# analog_homoThermistor_3xChannel_R1.net
KiCad netlist of a schematic drawn in EAGLE
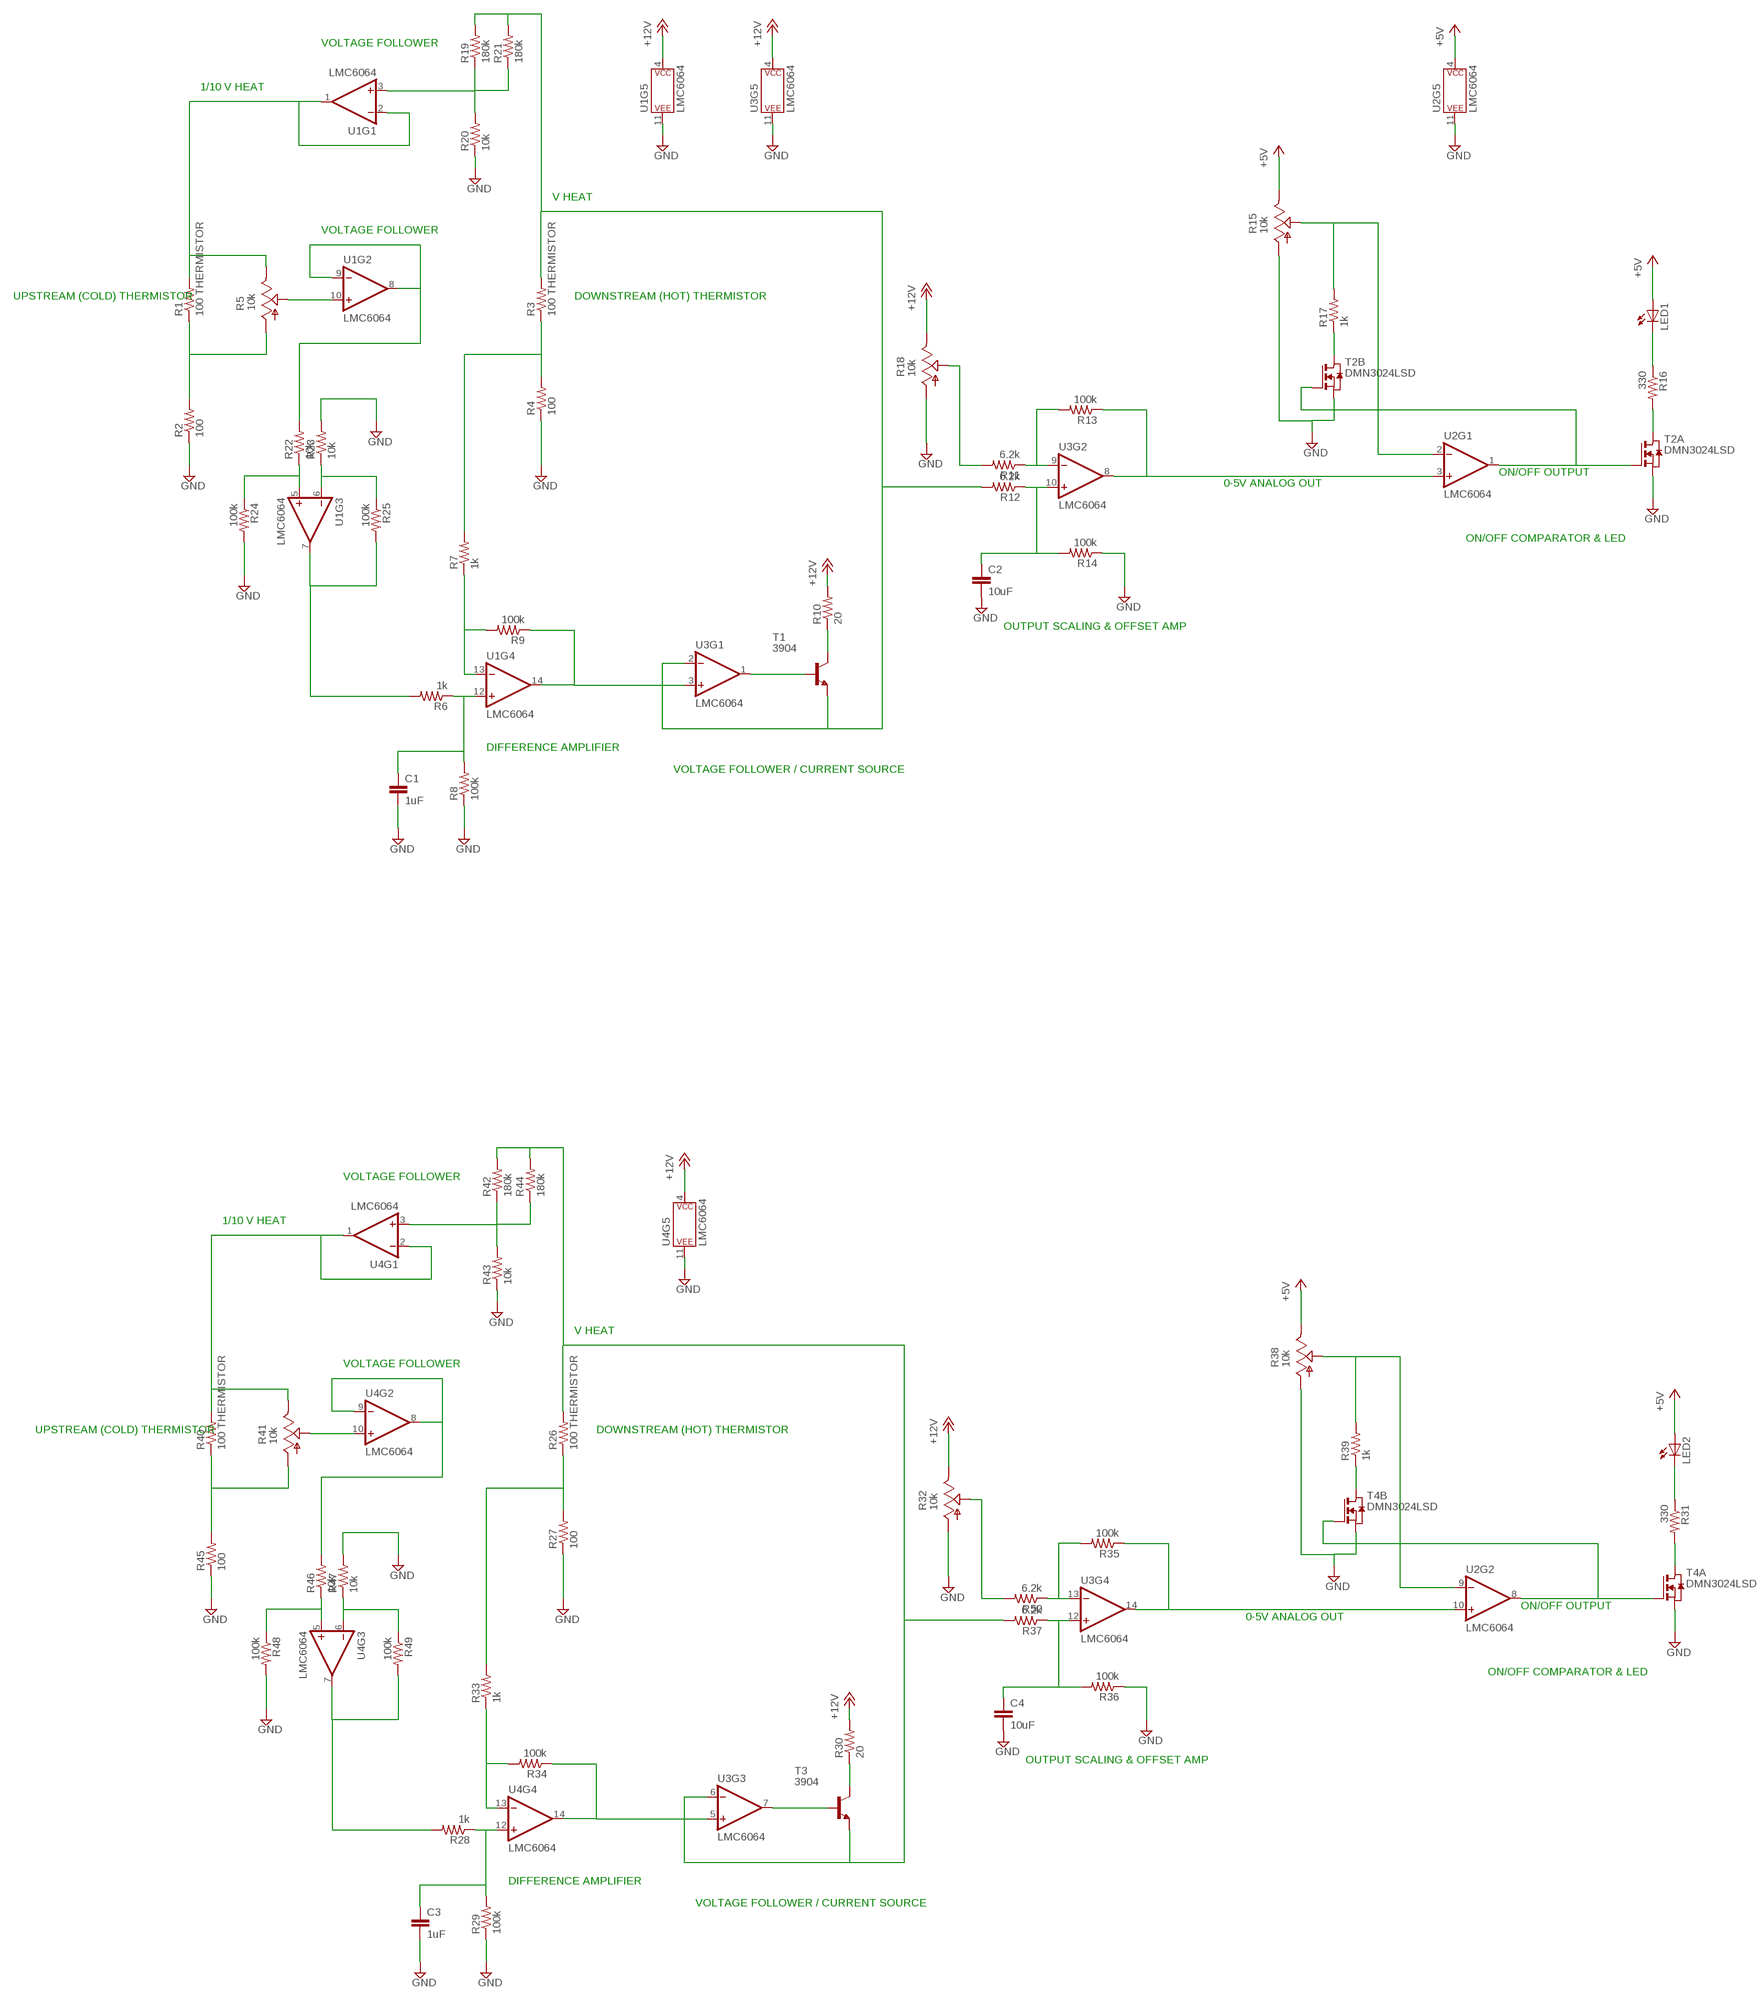
[diagram p0: schematic, sheet 1, part 1 of 2]
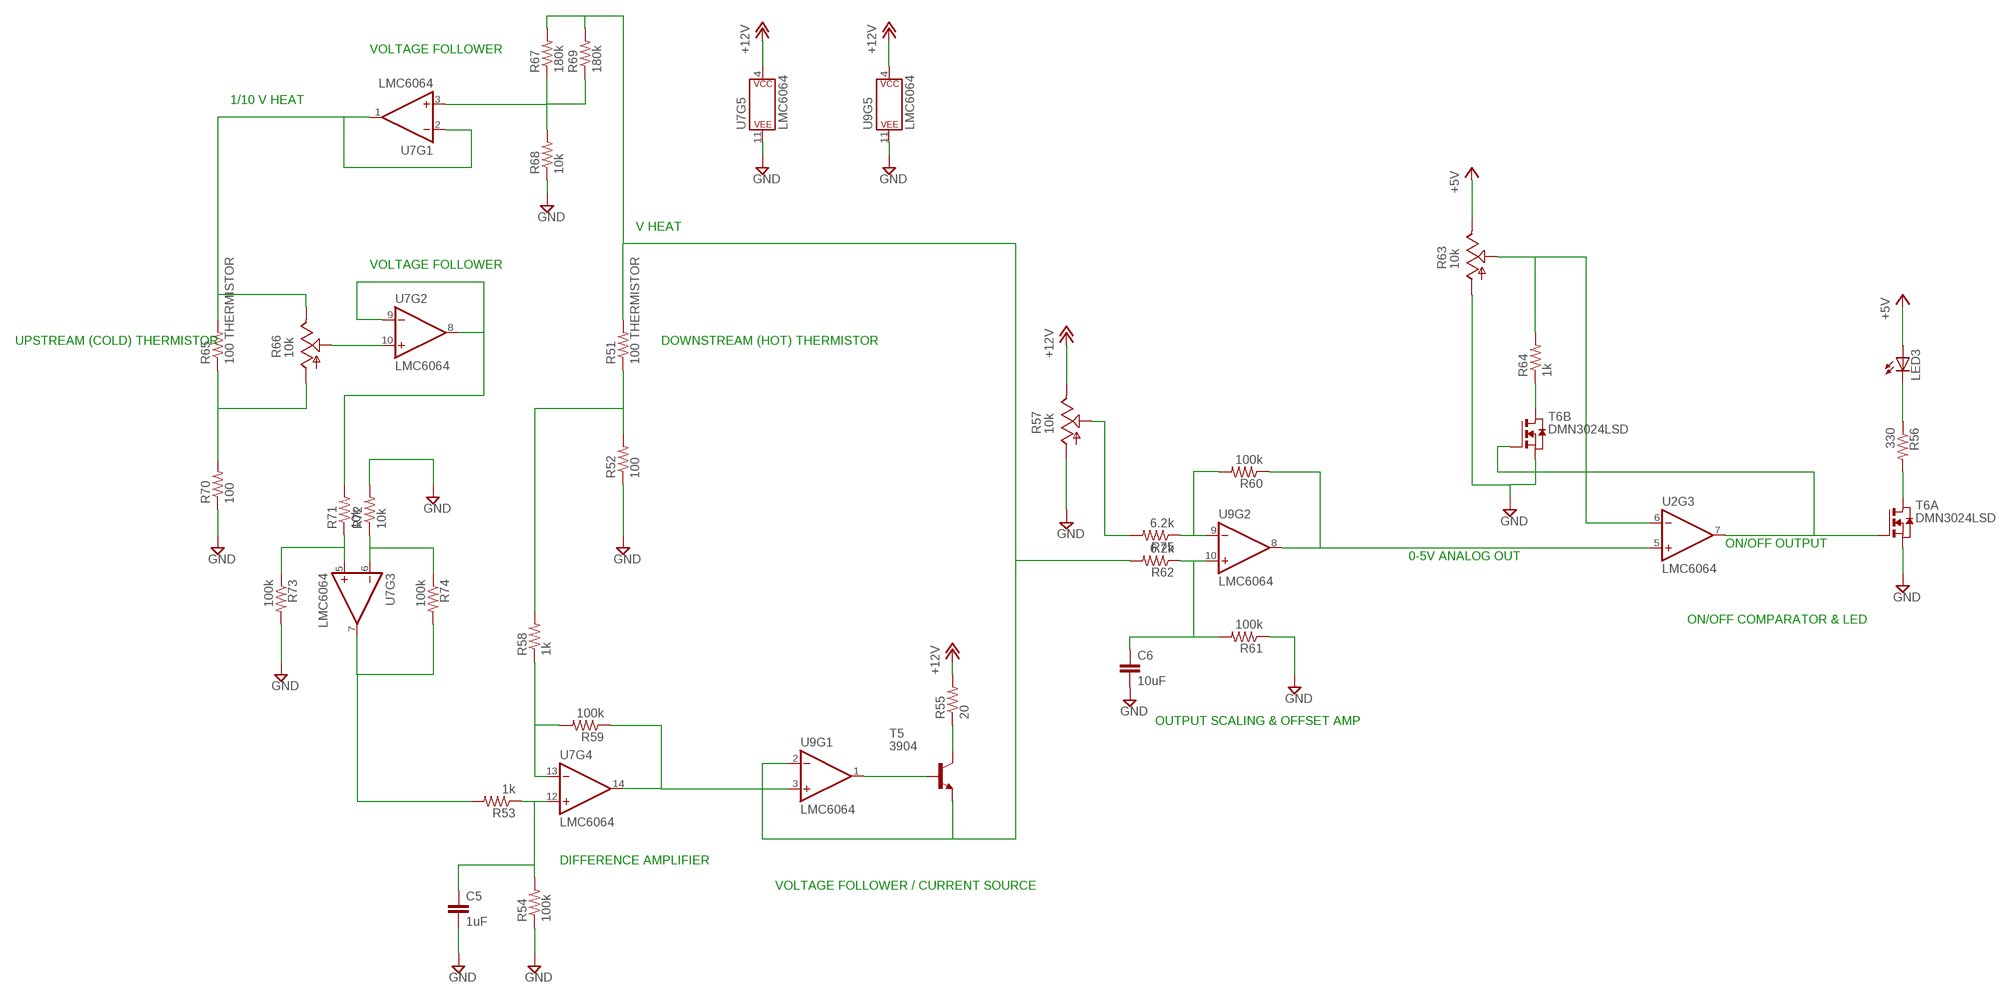
[diagram p1: schematic, sheet 1, part 2 of 2]

(export (version "E")
  (design (tool "Eeschema 10.0.6"))
  (components
    (comp (ref "C1")
      (value "1uF")
      (footprint "eagle-import:C0603")
      (fields
        (field (name "MF") "Murata Electronics North America")
        (field (name "MPN") "GRM188R61C105KA93D")
      )
      (libsource (lib "eagle-import") (part "C-EUC0603"))
    )
    (comp (ref "C2")
      (value "10uF")
      (footprint "eagle-import:C0603")
      (fields
        (field (name "MF") "Murata Electronics North America")
        (field (name "MPN") "GRM188C81C106MA73D")
      )
      (libsource (lib "eagle-import") (part "C-EUC0603"))
    )
    (comp (ref "C3")
      (value "1uF")
      (footprint "eagle-import:C0603")
      (fields
        (field (name "MF") "Murata Electronics North America")
        (field (name "MPN") "GRM188R61C105KA93D")
      )
      (libsource (lib "eagle-import") (part "C-EUC0603"))
    )
    (comp (ref "C4")
      (value "10uF")
      (footprint "eagle-import:C0603")
      (fields
        (field (name "MF") "Murata Electronics North America")
        (field (name "MPN") "GRM188C81C106MA73D")
      )
      (libsource (lib "eagle-import") (part "C-EUC0603"))
    )
    (comp (ref "C5")
      (value "1uF")
      (footprint "eagle-import:C0603")
      (fields
        (field (name "MF") "Murata Electronics North America")
        (field (name "MPN") "GRM188R61C105KA93D")
      )
      (libsource (lib "eagle-import") (part "C-EUC0603"))
    )
    (comp (ref "C6")
      (value "10uF")
      (footprint "eagle-import:C0603")
      (fields
        (field (name "MF") "Murata Electronics North America")
        (field (name "MPN") "GRM188C81C106MA73D")
      )
      (libsource (lib "eagle-import") (part "C-EUC0603"))
    )
    (comp (ref "LED1")
      (value "LEDCHIPLED_1206")
      (footprint "eagle-import:CHIPLED_1206")
      (fields (field (name "MF") "Lite-On Inc.") (field (name "MPN") "LTST-C150GKT"))
      (libsource (lib "eagle-import") (part "LEDCHIPLED_1206"))
    )
    (comp (ref "LED2")
      (value "LEDCHIPLED_1206")
      (footprint "eagle-import:CHIPLED_1206")
      (fields (field (name "MF") "Lite-On Inc.") (field (name "MPN") "LTST-C150GKT"))
      (libsource (lib "eagle-import") (part "LEDCHIPLED_1206"))
    )
    (comp (ref "LED3")
      (value "LEDCHIPLED_1206")
      (footprint "eagle-import:CHIPLED_1206")
      (fields (field (name "MF") "Lite-On Inc.") (field (name "MPN") "LTST-C150GKT"))
      (libsource (lib "eagle-import") (part "LEDCHIPLED_1206"))
    )
    (comp (ref "R1")
      (value "100 THERMISTOR")
      (footprint "eagle-import:R0603")
      (fields
        (field (name "DISTR") "Digikey")
        (field (name "DISTRPN") "490-2434-1-ND")
        (field (name "MF") "Murata Electronics North America")
        (field (name "MPN") "NCP18XF101J03RB")
      )
      (libsource (lib "eagle-import") (part "R-US_R0603"))
    )
    (comp (ref "R2")
      (value "100")
      (footprint "eagle-import:R0603")
      (fields (field (name "MF") "Panasonic Electronic Components") (field (name "MPN") "ERJ-PA3F1000V"))
      (libsource (lib "eagle-import") (part "R-US_R0603"))
    )
    (comp (ref "R3")
      (value "100 THERMISTOR")
      (footprint "eagle-import:R0603")
      (fields
        (field (name "DISTR") "Digikey")
        (field (name "DISTRPN") "490-2434-1-ND")
        (field (name "MF") "Murata Electronics North America")
        (field (name "MPN") "NCP18XF101J03RB")
      )
      (libsource (lib "eagle-import") (part "R-US_R0603"))
    )
    (comp (ref "R4")
      (value "100")
      (footprint "eagle-import:R0603")
      (fields (field (name "MF") "Panasonic Electronic Components") (field (name "MPN") "ERJ-PA3F1000V"))
      (libsource (lib "eagle-import") (part "R-US_R0603"))
    )
    (comp (ref "R5")
      (value "10k")
      (footprint "eagle-import:SM-42_43W")
      (fields (field (name "MF") "Copal Electronics Inc.") (field (name "MPN") "SM-42TW103"))
      (libsource (lib "eagle-import") (part "TRIM_US-SM-42/43W"))
    )
    (comp (ref "R6")
      (value "1k")
      (footprint "eagle-import:R0603")
      (fields (field (name "MF") "Panasonic Electronic Components") (field (name "MPN") "ERJ-PA3F1001V"))
      (libsource (lib "eagle-import") (part "R-US_R0603"))
    )
    (comp (ref "R7")
      (value "1k")
      (footprint "eagle-import:R0603")
      (fields (field (name "MF") "Panasonic Electronic Components") (field (name "MPN") "ERJ-PA3F1001V"))
      (libsource (lib "eagle-import") (part "R-US_R0603"))
    )
    (comp (ref "R8")
      (value "100k")
      (footprint "eagle-import:R0603")
      (fields (field (name "MF") "Panasonic Electronic Components") (field (name "MPN") "ERJ-PA3F1003V"))
      (libsource (lib "eagle-import") (part "R-US_R0603"))
    )
    (comp (ref "R9")
      (value "100k")
      (footprint "eagle-import:R0603")
      (fields (field (name "MF") "Panasonic Electronic Components") (field (name "MPN") "ERJ-PA3F1003V"))
      (libsource (lib "eagle-import") (part "R-US_R0603"))
    )
    (comp (ref "R10")
      (value "20")
      (footprint "eagle-import:R0603")
      (fields (field (name "MF") "Panasonic Electronic Components") (field (name "MPN") "ERJ-PA3F20R0V"))
      (libsource (lib "eagle-import") (part "R-US_R0603"))
    )
    (comp (ref "R11")
      (value "6.2k")
      (footprint "eagle-import:R0603")
      (fields (field (name "MF") "Panasonic Electronic Components") (field (name "MPN") "ERJ-PA3F6201V"))
      (libsource (lib "eagle-import") (part "R-US_R0603"))
    )
    (comp (ref "R12")
      (value "6.2k")
      (footprint "eagle-import:R0603")
      (fields (field (name "MF") "Panasonic Electronic Components") (field (name "MPN") "ERJ-PA3F6201V"))
      (libsource (lib "eagle-import") (part "R-US_R0603"))
    )
    (comp (ref "R13")
      (value "100k")
      (footprint "eagle-import:R0603")
      (fields (field (name "MF") "Panasonic Electronic Components") (field (name "MPN") "ERJ-PA3F1003V"))
      (libsource (lib "eagle-import") (part "R-US_R0603"))
    )
    (comp (ref "R14")
      (value "100k")
      (footprint "eagle-import:R0603")
      (fields (field (name "MF") "Panasonic Electronic Components") (field (name "MPN") "ERJ-PA3F1003V"))
      (libsource (lib "eagle-import") (part "R-US_R0603"))
    )
    (comp (ref "R15")
      (value "10k")
      (footprint "eagle-import:SM-42_43W")
      (fields (field (name "MF") "Copal Electronics Inc.") (field (name "MPN") "SM-42TW103"))
      (libsource (lib "eagle-import") (part "TRIM_US-SM-42/43W"))
    )
    (comp (ref "R16")
      (value "330")
      (footprint "eagle-import:R0603")
      (fields (field (name "MF") "Panasonic Electronic Components") (field (name "MPN") "ERJ-PA3F3300V"))
      (libsource (lib "eagle-import") (part "R-US_R0603"))
    )
    (comp (ref "R17")
      (value "1k")
      (footprint "eagle-import:R0603")
      (fields (field (name "MF") "Panasonic Electronic Components") (field (name "MPN") "ERJ-PA3F1001V"))
      (libsource (lib "eagle-import") (part "R-US_R0603"))
    )
    (comp (ref "R18")
      (value "10k")
      (footprint "eagle-import:SM-42_43W")
      (fields (field (name "MF") "Copal Electronics Inc.") (field (name "MPN") "SM-42TW103"))
      (libsource (lib "eagle-import") (part "TRIM_US-SM-42/43W"))
    )
    (comp (ref "R19")
      (value "180k")
      (footprint "eagle-import:R0603")
      (fields (field (name "MF") "Panasonic Electronic Components") (field (name "MPN") "ERJ-PA3F1803V"))
      (libsource (lib "eagle-import") (part "R-US_R0603"))
    )
    (comp (ref "R20")
      (value "10k")
      (footprint "eagle-import:R0603")
      (fields (field (name "MF") "Panasonic Electronic Components") (field (name "MPN") "ERJ-PA3F1002V"))
      (libsource (lib "eagle-import") (part "R-US_R0603"))
    )
    (comp (ref "R21")
      (value "180k")
      (footprint "eagle-import:R0603")
      (fields (field (name "MF") "Panasonic Electronic Components") (field (name "MPN") "ERJ-PA3F1803V"))
      (libsource (lib "eagle-import") (part "R-US_R0603"))
    )
    (comp (ref "R22")
      (value "10k")
      (footprint "eagle-import:R0603")
      (fields (field (name "MF") "Panasonic Electronic Components") (field (name "MPN") "ERJ-PA3F1002V"))
      (libsource (lib "eagle-import") (part "R-US_R0603"))
    )
    (comp (ref "R23")
      (value "10k")
      (footprint "eagle-import:R0603")
      (fields (field (name "MF") "Panasonic Electronic Components") (field (name "MPN") "ERJ-PA3F1002V"))
      (libsource (lib "eagle-import") (part "R-US_R0603"))
    )
    (comp (ref "R24")
      (value "100k")
      (footprint "eagle-import:R0603")
      (fields (field (name "MF") "Panasonic Electronic Components") (field (name "MPN") "ERJ-PA3F1003V"))
      (libsource (lib "eagle-import") (part "R-US_R0603"))
    )
    (comp (ref "R25")
      (value "100k")
      (footprint "eagle-import:R0603")
      (fields (field (name "MF") "Panasonic Electronic Components") (field (name "MPN") "ERJ-PA3F1003V"))
      (libsource (lib "eagle-import") (part "R-US_R0603"))
    )
    (comp (ref "R26")
      (value "100 THERMISTOR")
      (footprint "eagle-import:R0603")
      (fields
        (field (name "DISTR") "Digikey")
        (field (name "DISTRPN") "490-2434-1-ND")
        (field (name "MF") "Murata Electronics North America")
        (field (name "MPN") "NCP18XF101J03RB")
      )
      (libsource (lib "eagle-import") (part "R-US_R0603"))
    )
    (comp (ref "R27")
      (value "100")
      (footprint "eagle-import:R0603")
      (fields (field (name "MF") "Panasonic Electronic Components") (field (name "MPN") "ERJ-PA3F1000V"))
      (libsource (lib "eagle-import") (part "R-US_R0603"))
    )
    (comp (ref "R28")
      (value "1k")
      (footprint "eagle-import:R0603")
      (fields (field (name "MF") "Panasonic Electronic Components") (field (name "MPN") "ERJ-PA3F1001V"))
      (libsource (lib "eagle-import") (part "R-US_R0603"))
    )
    (comp (ref "R29")
      (value "100k")
      (footprint "eagle-import:R0603")
      (fields (field (name "MF") "Panasonic Electronic Components") (field (name "MPN") "ERJ-PA3F1003V"))
      (libsource (lib "eagle-import") (part "R-US_R0603"))
    )
    (comp (ref "R30")
      (value "20")
      (footprint "eagle-import:R0603")
      (fields (field (name "MF") "Panasonic Electronic Components") (field (name "MPN") "ERJ-PA3F20R0V"))
      (libsource (lib "eagle-import") (part "R-US_R0603"))
    )
    (comp (ref "R31")
      (value "330")
      (footprint "eagle-import:R0603")
      (fields (field (name "MF") "Panasonic Electronic Components") (field (name "MPN") "ERJ-PA3F3300V"))
      (libsource (lib "eagle-import") (part "R-US_R0603"))
    )
    (comp (ref "R32")
      (value "10k")
      (footprint "eagle-import:SM-42_43W")
      (fields (field (name "MF") "Copal Electronics Inc.") (field (name "MPN") "SM-42TW103"))
      (libsource (lib "eagle-import") (part "TRIM_US-SM-42/43W"))
    )
    (comp (ref "R33")
      (value "1k")
      (footprint "eagle-import:R0603")
      (fields (field (name "MF") "Panasonic Electronic Components") (field (name "MPN") "ERJ-PA3F1001V"))
      (libsource (lib "eagle-import") (part "R-US_R0603"))
    )
    (comp (ref "R34")
      (value "100k")
      (footprint "eagle-import:R0603")
      (fields (field (name "MF") "Panasonic Electronic Components") (field (name "MPN") "ERJ-PA3F1003V"))
      (libsource (lib "eagle-import") (part "R-US_R0603"))
    )
    (comp (ref "R35")
      (value "100k")
      (footprint "eagle-import:R0603")
      (fields (field (name "MF") "Panasonic Electronic Components") (field (name "MPN") "ERJ-PA3F1003V"))
      (libsource (lib "eagle-import") (part "R-US_R0603"))
    )
    (comp (ref "R36")
      (value "100k")
      (footprint "eagle-import:R0603")
      (fields (field (name "MF") "Panasonic Electronic Components") (field (name "MPN") "ERJ-PA3F1003V"))
      (libsource (lib "eagle-import") (part "R-US_R0603"))
    )
    (comp (ref "R37")
      (value "6.2k")
      (footprint "eagle-import:R0603")
      (fields (field (name "MF") "Panasonic Electronic Components") (field (name "MPN") "ERJ-PA3F6201V"))
      (libsource (lib "eagle-import") (part "R-US_R0603"))
    )
    (comp (ref "R38")
      (value "10k")
      (footprint "eagle-import:SM-42_43W")
      (fields (field (name "MF") "Copal Electronics Inc.") (field (name "MPN") "SM-42TW103"))
      (libsource (lib "eagle-import") (part "TRIM_US-SM-42/43W"))
    )
    (comp (ref "R39")
      (value "1k")
      (footprint "eagle-import:R0603")
      (fields (field (name "MF") "Panasonic Electronic Components") (field (name "MPN") "ERJ-PA3F1001V"))
      (libsource (lib "eagle-import") (part "R-US_R0603"))
    )
    (comp (ref "R40")
      (value "100 THERMISTOR")
      (footprint "eagle-import:R0603")
      (fields
        (field (name "DISTR") "Digikey")
        (field (name "DISTRPN") "490-2434-1-ND")
        (field (name "MF") "Murata Electronics North America")
        (field (name "MPN") "NCP18XF101J03RB")
      )
      (libsource (lib "eagle-import") (part "R-US_R0603"))
    )
    (comp (ref "R41")
      (value "10k")
      (footprint "eagle-import:SM-42_43W")
      (fields (field (name "MF") "Copal Electronics Inc.") (field (name "MPN") "SM-42TW103"))
      (libsource (lib "eagle-import") (part "TRIM_US-SM-42/43W"))
    )
    (comp (ref "R42")
      (value "180k")
      (footprint "eagle-import:R0603")
      (fields (field (name "MF") "Panasonic Electronic Components") (field (name "MPN") "ERJ-PA3F1803V"))
      (libsource (lib "eagle-import") (part "R-US_R0603"))
    )
    (comp (ref "R43")
      (value "10k")
      (footprint "eagle-import:R0603")
      (fields (field (name "MF") "Panasonic Electronic Components") (field (name "MPN") "ERJ-PA3F1002V"))
      (libsource (lib "eagle-import") (part "R-US_R0603"))
    )
    (comp (ref "R44")
      (value "180k")
      (footprint "eagle-import:R0603")
      (fields (field (name "MF") "Panasonic Electronic Components") (field (name "MPN") "ERJ-PA3F1803V"))
      (libsource (lib "eagle-import") (part "R-US_R0603"))
    )
    (comp (ref "R45")
      (value "100")
      (footprint "eagle-import:R0603")
      (fields (field (name "MF") "Panasonic Electronic Components") (field (name "MPN") "ERJ-PA3F1000V"))
      (libsource (lib "eagle-import") (part "R-US_R0603"))
    )
    (comp (ref "R46")
      (value "10k")
      (footprint "eagle-import:R0603")
      (fields (field (name "MF") "Panasonic Electronic Components") (field (name "MPN") "ERJ-PA3F1002V"))
      (libsource (lib "eagle-import") (part "R-US_R0603"))
    )
    (comp (ref "R47")
      (value "10k")
      (footprint "eagle-import:R0603")
      (fields (field (name "MF") "Panasonic Electronic Components") (field (name "MPN") "ERJ-PA3F1002V"))
      (libsource (lib "eagle-import") (part "R-US_R0603"))
    )
    (comp (ref "R48")
      (value "100k")
      (footprint "eagle-import:R0603")
      (fields (field (name "MF") "Panasonic Electronic Components") (field (name "MPN") "ERJ-PA3F1003V"))
      (libsource (lib "eagle-import") (part "R-US_R0603"))
    )
    (comp (ref "R49")
      (value "100k")
      (footprint "eagle-import:R0603")
      (fields (field (name "MF") "Panasonic Electronic Components") (field (name "MPN") "ERJ-PA3F1003V"))
      (libsource (lib "eagle-import") (part "R-US_R0603"))
    )
    (comp (ref "R50")
      (value "6.2k")
      (footprint "eagle-import:R0603")
      (fields (field (name "MF") "Panasonic Electronic Components") (field (name "MPN") "ERJ-PA3F6201V"))
      (libsource (lib "eagle-import") (part "R-US_R0603"))
    )
    (comp (ref "R51")
      (value "100 THERMISTOR")
      (footprint "eagle-import:R0603")
      (fields
        (field (name "DISTR") "Digikey")
        (field (name "DISTRPN") "490-2434-1-ND")
        (field (name "MF") "Murata Electronics North America")
        (field (name "MPN") "NCP18XF101J03RB")
      )
      (libsource (lib "eagle-import") (part "R-US_R0603"))
    )
    (comp (ref "R52")
      (value "100")
      (footprint "eagle-import:R0603")
      (fields (field (name "MF") "Panasonic Electronic Components") (field (name "MPN") "ERJ-PA3F1000V"))
      (libsource (lib "eagle-import") (part "R-US_R0603"))
    )
    (comp (ref "R53")
      (value "1k")
      (footprint "eagle-import:R0603")
      (fields (field (name "MF") "Panasonic Electronic Components") (field (name "MPN") "ERJ-PA3F1001V"))
      (libsource (lib "eagle-import") (part "R-US_R0603"))
    )
    (comp (ref "R54")
      (value "100k")
      (footprint "eagle-import:R0603")
      (fields (field (name "MF") "Panasonic Electronic Components") (field (name "MPN") "ERJ-PA3F1003V"))
      (libsource (lib "eagle-import") (part "R-US_R0603"))
    )
    (comp (ref "R55")
      (value "20")
      (footprint "eagle-import:R0603")
      (fields (field (name "MF") "Panasonic Electronic Components") (field (name "MPN") "ERJ-PA3F20R0V"))
      (libsource (lib "eagle-import") (part "R-US_R0603"))
    )
    (comp (ref "R56")
      (value "330")
      (footprint "eagle-import:R0603")
      (fields (field (name "MF") "Panasonic Electronic Components") (field (name "MPN") "ERJ-PA3F3300V"))
      (libsource (lib "eagle-import") (part "R-US_R0603"))
    )
    (comp (ref "R57")
      (value "10k")
      (footprint "eagle-import:SM-42_43W")
      (fields (field (name "MF") "Copal Electronics Inc.") (field (name "MPN") "SM-42TW103"))
      (libsource (lib "eagle-import") (part "TRIM_US-SM-42/43W"))
    )
    (comp (ref "R58")
      (value "1k")
      (footprint "eagle-import:R0603")
      (fields (field (name "MF") "Panasonic Electronic Components") (field (name "MPN") "ERJ-PA3F1001V"))
      (libsource (lib "eagle-import") (part "R-US_R0603"))
    )
    (comp (ref "R59")
      (value "100k")
      (footprint "eagle-import:R0603")
      (fields (field (name "MF") "Panasonic Electronic Components") (field (name "MPN") "ERJ-PA3F1003V"))
      (libsource (lib "eagle-import") (part "R-US_R0603"))
    )
    (comp (ref "R60")
      (value "100k")
      (footprint "eagle-import:R0603")
      (fields (field (name "MF") "Panasonic Electronic Components") (field (name "MPN") "ERJ-PA3F1003V"))
      (libsource (lib "eagle-import") (part "R-US_R0603"))
    )
    (comp (ref "R61")
      (value "100k")
      (footprint "eagle-import:R0603")
      (fields (field (name "MF") "Panasonic Electronic Components") (field (name "MPN") "ERJ-PA3F1003V"))
      (libsource (lib "eagle-import") (part "R-US_R0603"))
    )
    (comp (ref "R62")
      (value "6.2k")
      (footprint "eagle-import:R0603")
      (fields (field (name "MF") "Panasonic Electronic Components") (field (name "MPN") "ERJ-PA3F6201V"))
      (libsource (lib "eagle-import") (part "R-US_R0603"))
    )
    (comp (ref "R63")
      (value "10k")
      (footprint "eagle-import:SM-42_43W")
      (fields (field (name "MF") "Copal Electronics Inc.") (field (name "MPN") "SM-42TW103"))
      (libsource (lib "eagle-import") (part "TRIM_US-SM-42/43W"))
    )
    (comp (ref "R64")
      (value "1k")
      (footprint "eagle-import:R0603")
      (fields (field (name "MF") "Panasonic Electronic Components") (field (name "MPN") "ERJ-PA3F1001V"))
      (libsource (lib "eagle-import") (part "R-US_R0603"))
    )
    (comp (ref "R65")
      (value "100 THERMISTOR")
      (footprint "eagle-import:R0603")
      (fields
        (field (name "DISTR") "Digikey")
        (field (name "DISTRPN") "490-2434-1-ND")
        (field (name "MF") "Murata Electronics North America")
        (field (name "MPN") "NCP18XF101J03RB")
      )
      (libsource (lib "eagle-import") (part "R-US_R0603"))
    )
    (comp (ref "R66")
      (value "10k")
      (footprint "eagle-import:SM-42_43W")
      (fields (field (name "MF") "Copal Electronics Inc.") (field (name "MPN") "SM-42TW103"))
      (libsource (lib "eagle-import") (part "TRIM_US-SM-42/43W"))
    )
    (comp (ref "R67")
      (value "180k")
      (footprint "eagle-import:R0603")
      (fields (field (name "MF") "Panasonic Electronic Components") (field (name "MPN") "ERJ-PA3F1803V"))
      (libsource (lib "eagle-import") (part "R-US_R0603"))
    )
    (comp (ref "R68")
      (value "10k")
      (footprint "eagle-import:R0603")
      (fields (field (name "MF") "Panasonic Electronic Components") (field (name "MPN") "ERJ-PA3F1002V"))
      (libsource (lib "eagle-import") (part "R-US_R0603"))
    )
    (comp (ref "R69")
      (value "180k")
      (footprint "eagle-import:R0603")
      (fields (field (name "MF") "Panasonic Electronic Components") (field (name "MPN") "ERJ-PA3F1803V"))
      (libsource (lib "eagle-import") (part "R-US_R0603"))
    )
    (comp (ref "R70")
      (value "100")
      (footprint "eagle-import:R0603")
      (fields (field (name "MF") "Panasonic Electronic Components") (field (name "MPN") "ERJ-PA3F1000V"))
      (libsource (lib "eagle-import") (part "R-US_R0603"))
    )
    (comp (ref "R71")
      (value "10k")
      (footprint "eagle-import:R0603")
      (fields (field (name "MF") "Panasonic Electronic Components") (field (name "MPN") "ERJ-PA3F1002V"))
      (libsource (lib "eagle-import") (part "R-US_R0603"))
    )
    (comp (ref "R72")
      (value "10k")
      (footprint "eagle-import:R0603")
      (fields (field (name "MF") "Panasonic Electronic Components") (field (name "MPN") "ERJ-PA3F1002V"))
      (libsource (lib "eagle-import") (part "R-US_R0603"))
    )
    (comp (ref "R73")
      (value "100k")
      (footprint "eagle-import:R0603")
      (fields (field (name "MF") "Panasonic Electronic Components") (field (name "MPN") "ERJ-PA3F1003V"))
      (libsource (lib "eagle-import") (part "R-US_R0603"))
    )
    (comp (ref "R74")
      (value "100k")
      (footprint "eagle-import:R0603")
      (fields (field (name "MF") "Panasonic Electronic Components") (field (name "MPN") "ERJ-PA3F1003V"))
      (libsource (lib "eagle-import") (part "R-US_R0603"))
    )
    (comp (ref "R75")
      (value "6.2k")
      (footprint "eagle-import:R0603")
      (fields (field (name "MF") "Panasonic Electronic Components") (field (name "MPN") "ERJ-PA3F6201V"))
      (libsource (lib "eagle-import") (part "R-US_R0603"))
    )
    (comp (ref "T1")
      (value "3904")
      (footprint "eagle-import:SOT23-BEC")
      (fields (field (name "MF") "Fairchild/ON Semiconductor") (field (name "MPN") "MMBT3904"))
      (libsource (lib "eagle-import") (part "-NPN-SOT23-BECMMBT3904LT1"))
    )
    (comp (ref "T2")
      (value "DMN3024LSD")
      (footprint "eagle-import:SO8")
      (fields
        (field (name "MF") "Diodes Incorporated")
        (field (name "MPN") "DMN3024LSD-13")
        (field (name "DISTR") "Digikey")
        (field (name "DISTRPN") "DMN3024LSD-13DICT-ND")
      )
      (libsource (lib "eagle-import") (part "DMN3024LSD"))
    )
    (comp (ref "T3")
      (value "3904")
      (footprint "eagle-import:SOT23-BEC")
      (fields (field (name "MF") "Fairchild/ON Semiconductor") (field (name "MPN") "MMBT3904"))
      (libsource (lib "eagle-import") (part "-NPN-SOT23-BECMMBT3904LT1"))
    )
    (comp (ref "T4")
      (value "DMN3024LSD")
      (footprint "eagle-import:SO8")
      (fields
        (field (name "DISTR") "Digikey")
        (field (name "DISTRPN") "DMN3024LSD-13DICT-ND")
        (field (name "MF") "Diodes Incorporated")
        (field (name "MPN") "DMN3024LSD-13")
      )
      (libsource (lib "eagle-import") (part "DMN3024LSD"))
    )
    (comp (ref "T5")
      (value "3904")
      (footprint "eagle-import:SOT23-BEC")
      (fields (field (name "MF") "Fairchild/ON Semiconductor") (field (name "MPN") "MMBT3904"))
      (libsource (lib "eagle-import") (part "-NPN-SOT23-BECMMBT3904LT1"))
    )
    (comp (ref "T6")
      (value "DMN3024LSD")
      (footprint "eagle-import:SO8")
      (fields
        (field (name "MF") "Diodes Incorporated")
        (field (name "MPN") "DMN3024LSD-13")
        (field (name "DISTR") "Digikey")
        (field (name "DISTRPN") "DMN3024LSD-13DICT-ND")
      )
      (libsource (lib "eagle-import") (part "DMN3024LSD"))
    )
    (comp (ref "U1")
      (value "LMC6064")
      (footprint "eagle-import:SO14")
      (fields
        (field (name "DISTR") "Digikey")
        (field (name "DISTRPN") "296-35438-1-ND")
        (field (name "MF") "Texas Instruments")
        (field (name "MPN") "LMC6064AIMX/NOPB")
      )
      (libsource (lib "eagle-import") (part "LMC6064"))
    )
    (comp (ref "U2")
      (value "LMC6064")
      (footprint "eagle-import:SO14")
      (fields
        (field (name "DISTR") "Digikey")
        (field (name "DISTRPN") "296-35438-1-ND")
        (field (name "MF") "Texas Instruments")
        (field (name "MPN") "LMC6064AIMX/NOPB")
      )
      (libsource (lib "eagle-import") (part "LMC6064"))
    )
    (comp (ref "U3")
      (value "LMC6064")
      (footprint "eagle-import:SO14")
      (fields
        (field (name "DISTR") "Digikey")
        (field (name "DISTRPN") "296-35438-1-ND")
        (field (name "MF") "Texas Instruments")
        (field (name "MPN") "LMC6064AIMX/NOPB")
      )
      (libsource (lib "eagle-import") (part "LMC6064"))
    )
    (comp (ref "U4")
      (value "LMC6064")
      (footprint "eagle-import:SO14")
      (fields
        (field (name "DISTR") "Digikey")
        (field (name "DISTRPN") "296-35438-1-ND")
        (field (name "MF") "Texas Instruments")
        (field (name "MPN") "LMC6064AIMX/NOPB")
      )
      (libsource (lib "eagle-import") (part "LMC6064"))
    )
    (comp (ref "U7")
      (value "LMC6064")
      (footprint "eagle-import:SO14")
      (fields
        (field (name "DISTR") "Digikey")
        (field (name "DISTRPN") "296-35438-1-ND")
        (field (name "MF") "Texas Instruments")
        (field (name "MPN") "LMC6064AIMX/NOPB")
      )
      (libsource (lib "eagle-import") (part "LMC6064"))
    )
    (comp (ref "U9")
      (value "LMC6064")
      (footprint "eagle-import:SO14")
      (fields
        (field (name "DISTR") "Digikey")
        (field (name "DISTRPN") "296-35438-1-ND")
        (field (name "MF") "Texas Instruments")
        (field (name "MPN") "LMC6064AIMX/NOPB")
      )
      (libsource (lib "eagle-import") (part "LMC6064"))
    )
  )
  (nets
    (net (code "1") (name "+5V") (class "Default")
      (node (ref "LED1") (pin "A") (pinfunction "A_A") (pintype "passive"))
      (node (ref "LED2") (pin "A") (pinfunction "A_A") (pintype "passive"))
      (node (ref "LED3") (pin "A") (pinfunction "A_A") (pintype "passive"))
      (node (ref "R15") (pin "3") (pinfunction "E_3") (pintype "passive"))
      (node (ref "R38") (pin "3") (pinfunction "E_3") (pintype "passive"))
      (node (ref "R63") (pin "3") (pinfunction "E_3") (pintype "passive"))
      (node (ref "U2") (pin "4") (pinfunction "P$V+_4") (pintype "bidirectional"))
    )
    (net (code "2") (name "+12V") (class "Default")
      (node (ref "R10") (pin "2") (pinfunction "2_2") (pintype "passive"))
      (node (ref "R18") (pin "3") (pinfunction "E_3") (pintype "passive"))
      (node (ref "R30") (pin "2") (pinfunction "2_2") (pintype "passive"))
      (node (ref "R32") (pin "3") (pinfunction "E_3") (pintype "passive"))
      (node (ref "R55") (pin "2") (pinfunction "2_2") (pintype "passive"))
      (node (ref "R57") (pin "3") (pinfunction "E_3") (pintype "passive"))
      (node (ref "U1") (pin "4") (pinfunction "P$V+_4") (pintype "bidirectional"))
      (node (ref "U3") (pin "4") (pinfunction "P$V+_4") (pintype "bidirectional"))
      (node (ref "U4") (pin "4") (pinfunction "P$V+_4") (pintype "bidirectional"))
      (node (ref "U7") (pin "4") (pinfunction "P$V+_4") (pintype "bidirectional"))
      (node (ref "U9") (pin "4") (pinfunction "P$V+_4") (pintype "bidirectional"))
    )
    (net (code "3") (name "GND") (class "Default")
      (node (ref "C1") (pin "2") (pinfunction "2_2") (pintype "passive"))
      (node (ref "C2") (pin "2") (pinfunction "2_2") (pintype "passive"))
      (node (ref "C3") (pin "2") (pinfunction "2_2") (pintype "passive"))
      (node (ref "C4") (pin "2") (pinfunction "2_2") (pintype "passive"))
      (node (ref "C5") (pin "2") (pinfunction "2_2") (pintype "passive"))
      (node (ref "C6") (pin "2") (pinfunction "2_2") (pintype "passive"))
      (node (ref "R14") (pin "1") (pinfunction "1_1") (pintype "passive"))
      (node (ref "R15") (pin "1") (pinfunction "A_1") (pintype "passive"))
      (node (ref "R18") (pin "1") (pinfunction "A_1") (pintype "passive"))
      (node (ref "R2") (pin "1") (pinfunction "1_1") (pintype "passive"))
      (node (ref "R20") (pin "1") (pinfunction "1_1") (pintype "passive"))
      (node (ref "R23") (pin "2") (pinfunction "2_2") (pintype "passive"))
      (node (ref "R24") (pin "2") (pinfunction "2_2") (pintype "passive"))
      (node (ref "R27") (pin "1") (pinfunction "1_1") (pintype "passive"))
      (node (ref "R29") (pin "1") (pinfunction "1_1") (pintype "passive"))
      (node (ref "R32") (pin "1") (pinfunction "A_1") (pintype "passive"))
      (node (ref "R36") (pin "1") (pinfunction "1_1") (pintype "passive"))
      (node (ref "R38") (pin "1") (pinfunction "A_1") (pintype "passive"))
      (node (ref "R4") (pin "1") (pinfunction "1_1") (pintype "passive"))
      (node (ref "R43") (pin "1") (pinfunction "1_1") (pintype "passive"))
      (node (ref "R45") (pin "1") (pinfunction "1_1") (pintype "passive"))
      (node (ref "R47") (pin "2") (pinfunction "2_2") (pintype "passive"))
      (node (ref "R48") (pin "2") (pinfunction "2_2") (pintype "passive"))
      (node (ref "R52") (pin "1") (pinfunction "1_1") (pintype "passive"))
      (node (ref "R54") (pin "1") (pinfunction "1_1") (pintype "passive"))
      (node (ref "R57") (pin "1") (pinfunction "A_1") (pintype "passive"))
      (node (ref "R61") (pin "1") (pinfunction "1_1") (pintype "passive"))
      (node (ref "R63") (pin "1") (pinfunction "A_1") (pintype "passive"))
      (node (ref "R68") (pin "1") (pinfunction "1_1") (pintype "passive"))
      (node (ref "R70") (pin "1") (pinfunction "1_1") (pintype "passive"))
      (node (ref "R72") (pin "2") (pinfunction "2_2") (pintype "passive"))
      (node (ref "R73") (pin "2") (pinfunction "2_2") (pintype "passive"))
      (node (ref "R8") (pin "1") (pinfunction "1_1") (pintype "passive"))
      (node (ref "T2") (pin "1") (pinfunction "S_1") (pintype "passive"))
      (node (ref "T2") (pin "3") (pinfunction "S_3") (pintype "passive"))
      (node (ref "T4") (pin "1") (pinfunction "S_1") (pintype "passive"))
      (node (ref "T4") (pin "3") (pinfunction "S_3") (pintype "passive"))
      (node (ref "T6") (pin "1") (pinfunction "S_1") (pintype "passive"))
      (node (ref "T6") (pin "3") (pinfunction "S_3") (pintype "passive"))
      (node (ref "U1") (pin "11") (pinfunction "P$V-_11") (pintype "bidirectional"))
      (node (ref "U2") (pin "11") (pinfunction "P$V-_11") (pintype "bidirectional"))
      (node (ref "U3") (pin "11") (pinfunction "P$V-_11") (pintype "bidirectional"))
      (node (ref "U4") (pin "11") (pinfunction "P$V-_11") (pintype "bidirectional"))
      (node (ref "U7") (pin "11") (pinfunction "P$V-_11") (pintype "bidirectional"))
      (node (ref "U9") (pin "11") (pinfunction "P$V-_11") (pintype "bidirectional"))
    )
    (net (code "4") (name "Net-(LED1-PadC)") (class "Default")
      (node (ref "LED1") (pin "C") (pinfunction "C_C") (pintype "passive"))
      (node (ref "R16") (pin "1") (pinfunction "1_1") (pintype "passive"))
    )
    (net (code "5") (name "Net-(LED2-PadC)") (class "Default")
      (node (ref "LED2") (pin "C") (pinfunction "C_C") (pintype "passive"))
      (node (ref "R31") (pin "1") (pinfunction "1_1") (pintype "passive"))
    )
    (net (code "6") (name "Net-(LED3-PadC)") (class "Default")
      (node (ref "LED3") (pin "C") (pinfunction "C_C") (pintype "passive"))
      (node (ref "R56") (pin "1") (pinfunction "1_1") (pintype "passive"))
    )
    (net (code "7") (name "Net-(R3-Pad1)") (class "Default")
      (node (ref "R3") (pin "1") (pinfunction "1_1") (pintype "passive"))
      (node (ref "R4") (pin "2") (pinfunction "2_2") (pintype "passive"))
      (node (ref "R7") (pin "2") (pinfunction "2_2") (pintype "passive"))
    )
    (net (code "8") (name "Net-(R5-A)") (class "Default")
      (node (ref "R1") (pin "1") (pinfunction "1_1") (pintype "passive"))
      (node (ref "R2") (pin "2") (pinfunction "2_2") (pintype "passive"))
      (node (ref "R5") (pin "1") (pinfunction "A_1") (pintype "passive"))
    )
    (net (code "9") (name "Net-(R5-E)") (class "Default")
      (node (ref "R1") (pin "2") (pinfunction "2_2") (pintype "passive"))
      (node (ref "R5") (pin "3") (pinfunction "E_3") (pintype "passive"))
      (node (ref "U1") (pin "1") (pinfunction "OUT_1") (pintype "output"))
      (node (ref "U1") (pin "2") (pinfunction "-IN_2") (pintype "input"))
    )
    (net (code "10") (name "Net-(R5-S)") (class "Default")
      (node (ref "R5") (pin "2") (pinfunction "S_2") (pintype "passive"))
      (node (ref "U1") (pin "10") (pinfunction "+IN_10") (pintype "input"))
    )
    (net (code "11") (name "Net-(R10-Pad1)") (class "Default")
      (node (ref "R10") (pin "1") (pinfunction "1_1") (pintype "passive"))
      (node (ref "T1") (pin "C") (pinfunction "C_C") (pintype "passive"))
    )
    (net (code "12") (name "Net-(R15-S)") (class "Default")
      (node (ref "R15") (pin "2") (pinfunction "S_2") (pintype "passive"))
      (node (ref "R17") (pin "2") (pinfunction "2_2") (pintype "passive"))
      (node (ref "U2") (pin "2") (pinfunction "-IN_2") (pintype "input"))
    )
    (net (code "13") (name "Net-(R16-Pad2)") (class "Default")
      (node (ref "R16") (pin "2") (pinfunction "2_2") (pintype "passive"))
      (node (ref "T2") (pin "7") (pinfunction "D_7") (pintype "passive"))
      (node (ref "T2") (pin "8") (pinfunction "D_8") (pintype "passive"))
    )
    (net (code "14") (name "Net-(R17-Pad1)") (class "Default")
      (node (ref "R17") (pin "1") (pinfunction "1_1") (pintype "passive"))
      (node (ref "T2") (pin "5") (pinfunction "D_5") (pintype "passive"))
      (node (ref "T2") (pin "6") (pinfunction "D_6") (pintype "passive"))
    )
    (net (code "15") (name "Net-(R18-S)") (class "Default")
      (node (ref "R11") (pin "2") (pinfunction "2_2") (pintype "passive"))
      (node (ref "R18") (pin "2") (pinfunction "S_2") (pintype "passive"))
    )
    (net (code "16") (name "Net-(R26-Pad1)") (class "Default")
      (node (ref "R26") (pin "1") (pinfunction "1_1") (pintype "passive"))
      (node (ref "R27") (pin "2") (pinfunction "2_2") (pintype "passive"))
      (node (ref "R33") (pin "2") (pinfunction "2_2") (pintype "passive"))
    )
    (net (code "17") (name "Net-(R30-Pad1)") (class "Default")
      (node (ref "R30") (pin "1") (pinfunction "1_1") (pintype "passive"))
      (node (ref "T3") (pin "C") (pinfunction "C_C") (pintype "passive"))
    )
    (net (code "18") (name "Net-(R31-Pad2)") (class "Default")
      (node (ref "R31") (pin "2") (pinfunction "2_2") (pintype "passive"))
      (node (ref "T4") (pin "7") (pinfunction "D_7") (pintype "passive"))
      (node (ref "T4") (pin "8") (pinfunction "D_8") (pintype "passive"))
    )
    (net (code "19") (name "Net-(R32-S)") (class "Default")
      (node (ref "R32") (pin "2") (pinfunction "S_2") (pintype "passive"))
      (node (ref "R50") (pin "2") (pinfunction "2_2") (pintype "passive"))
    )
    (net (code "20") (name "Net-(R38-S)") (class "Default")
      (node (ref "R38") (pin "2") (pinfunction "S_2") (pintype "passive"))
      (node (ref "R39") (pin "2") (pinfunction "2_2") (pintype "passive"))
      (node (ref "U2") (pin "9") (pinfunction "-IN_9") (pintype "input"))
    )
    (net (code "21") (name "Net-(R39-Pad1)") (class "Default")
      (node (ref "R39") (pin "1") (pinfunction "1_1") (pintype "passive"))
      (node (ref "T4") (pin "5") (pinfunction "D_5") (pintype "passive"))
      (node (ref "T4") (pin "6") (pinfunction "D_6") (pintype "passive"))
    )
    (net (code "22") (name "Net-(R41-A)") (class "Default")
      (node (ref "R40") (pin "1") (pinfunction "1_1") (pintype "passive"))
      (node (ref "R41") (pin "1") (pinfunction "A_1") (pintype "passive"))
      (node (ref "R45") (pin "2") (pinfunction "2_2") (pintype "passive"))
    )
    (net (code "23") (name "Net-(R41-E)") (class "Default")
      (node (ref "R40") (pin "2") (pinfunction "2_2") (pintype "passive"))
      (node (ref "R41") (pin "3") (pinfunction "E_3") (pintype "passive"))
      (node (ref "U4") (pin "1") (pinfunction "OUT_1") (pintype "output"))
      (node (ref "U4") (pin "2") (pinfunction "-IN_2") (pintype "input"))
    )
    (net (code "24") (name "Net-(R41-S)") (class "Default")
      (node (ref "R41") (pin "2") (pinfunction "S_2") (pintype "passive"))
      (node (ref "U4") (pin "10") (pinfunction "+IN_10") (pintype "input"))
    )
    (net (code "25") (name "Net-(R51-Pad1)") (class "Default")
      (node (ref "R51") (pin "1") (pinfunction "1_1") (pintype "passive"))
      (node (ref "R52") (pin "2") (pinfunction "2_2") (pintype "passive"))
      (node (ref "R58") (pin "2") (pinfunction "2_2") (pintype "passive"))
    )
    (net (code "26") (name "Net-(R55-Pad1)") (class "Default")
      (node (ref "R55") (pin "1") (pinfunction "1_1") (pintype "passive"))
      (node (ref "T5") (pin "C") (pinfunction "C_C") (pintype "passive"))
    )
    (net (code "27") (name "Net-(R56-Pad2)") (class "Default")
      (node (ref "R56") (pin "2") (pinfunction "2_2") (pintype "passive"))
      (node (ref "T6") (pin "7") (pinfunction "D_7") (pintype "passive"))
      (node (ref "T6") (pin "8") (pinfunction "D_8") (pintype "passive"))
    )
    (net (code "28") (name "Net-(R57-S)") (class "Default")
      (node (ref "R57") (pin "2") (pinfunction "S_2") (pintype "passive"))
      (node (ref "R75") (pin "2") (pinfunction "2_2") (pintype "passive"))
    )
    (net (code "29") (name "Net-(R63-S)") (class "Default")
      (node (ref "R63") (pin "2") (pinfunction "S_2") (pintype "passive"))
      (node (ref "R64") (pin "2") (pinfunction "2_2") (pintype "passive"))
      (node (ref "U2") (pin "6") (pinfunction "-IN_6") (pintype "input"))
    )
    (net (code "30") (name "Net-(R64-Pad1)") (class "Default")
      (node (ref "R64") (pin "1") (pinfunction "1_1") (pintype "passive"))
      (node (ref "T6") (pin "5") (pinfunction "D_5") (pintype "passive"))
      (node (ref "T6") (pin "6") (pinfunction "D_6") (pintype "passive"))
    )
    (net (code "31") (name "Net-(R66-A)") (class "Default")
      (node (ref "R65") (pin "1") (pinfunction "1_1") (pintype "passive"))
      (node (ref "R66") (pin "1") (pinfunction "A_1") (pintype "passive"))
      (node (ref "R70") (pin "2") (pinfunction "2_2") (pintype "passive"))
    )
    (net (code "32") (name "Net-(R66-E)") (class "Default")
      (node (ref "R65") (pin "2") (pinfunction "2_2") (pintype "passive"))
      (node (ref "R66") (pin "3") (pinfunction "E_3") (pintype "passive"))
      (node (ref "U7") (pin "1") (pinfunction "OUT_1") (pintype "output"))
      (node (ref "U7") (pin "2") (pinfunction "-IN_2") (pintype "input"))
    )
    (net (code "33") (name "Net-(R66-S)") (class "Default")
      (node (ref "R66") (pin "2") (pinfunction "S_2") (pintype "passive"))
      (node (ref "U7") (pin "10") (pinfunction "+IN_10") (pintype "input"))
    )
    (net (code "34") (name "Net-(T2A-G)") (class "Default")
      (node (ref "T2") (pin "2") (pinfunction "G_2") (pintype "passive"))
      (node (ref "T2") (pin "4") (pinfunction "G_4") (pintype "passive"))
      (node (ref "U2") (pin "1") (pinfunction "OUT_1") (pintype "output"))
    )
    (net (code "35") (name "Net-(T4A-G)") (class "Default")
      (node (ref "T4") (pin "2") (pinfunction "G_2") (pintype "passive"))
      (node (ref "T4") (pin "4") (pinfunction "G_4") (pintype "passive"))
      (node (ref "U2") (pin "8") (pinfunction "OUT_8") (pintype "output"))
    )
    (net (code "36") (name "Net-(T6A-G)") (class "Default")
      (node (ref "T6") (pin "2") (pinfunction "G_2") (pintype "passive"))
      (node (ref "T6") (pin "4") (pinfunction "G_4") (pintype "passive"))
      (node (ref "U2") (pin "7") (pinfunction "OUT_7") (pintype "output"))
    )
    (net (code "37") (name "Net-(U1A-+IN)") (class "Default")
      (node (ref "R19") (pin "1") (pinfunction "1_1") (pintype "passive"))
      (node (ref "R20") (pin "2") (pinfunction "2_2") (pintype "passive"))
      (node (ref "R21") (pin "1") (pinfunction "1_1") (pintype "passive"))
      (node (ref "U1") (pin "3") (pinfunction "+IN_3") (pintype "input"))
    )
    (net (code "38") (name "Net-(U1B--IN)") (class "Default")
      (node (ref "R22") (pin "2") (pinfunction "2_2") (pintype "passive"))
      (node (ref "U1") (pin "8") (pinfunction "OUT_8") (pintype "output"))
      (node (ref "U1") (pin "9") (pinfunction "-IN_9") (pintype "input"))
    )
    (net (code "39") (name "Net-(U1C-+IN)") (class "Default")
      (node (ref "R22") (pin "1") (pinfunction "1_1") (pintype "passive"))
      (node (ref "R24") (pin "1") (pinfunction "1_1") (pintype "passive"))
      (node (ref "U1") (pin "5") (pinfunction "+IN_5") (pintype "input"))
    )
    (net (code "40") (name "Net-(U1C--IN)") (class "Default")
      (node (ref "R23") (pin "1") (pinfunction "1_1") (pintype "passive"))
      (node (ref "R25") (pin "1") (pinfunction "1_1") (pintype "passive"))
      (node (ref "U1") (pin "6") (pinfunction "-IN_6") (pintype "input"))
    )
    (net (code "41") (name "Net-(U1C-OUT)") (class "Default")
      (node (ref "R25") (pin "2") (pinfunction "2_2") (pintype "passive"))
      (node (ref "R6") (pin "2") (pinfunction "2_2") (pintype "passive"))
      (node (ref "U1") (pin "7") (pinfunction "OUT_7") (pintype "output"))
    )
    (net (code "42") (name "Net-(U1D-+IN)") (class "Default")
      (node (ref "C1") (pin "1") (pinfunction "1_1") (pintype "passive"))
      (node (ref "R6") (pin "1") (pinfunction "1_1") (pintype "passive"))
      (node (ref "R8") (pin "2") (pinfunction "2_2") (pintype "passive"))
      (node (ref "U1") (pin "12") (pinfunction "+IN_12") (pintype "input"))
    )
    (net (code "43") (name "Net-(U1D--IN)") (class "Default")
      (node (ref "R7") (pin "1") (pinfunction "1_1") (pintype "passive"))
      (node (ref "R9") (pin "2") (pinfunction "2_2") (pintype "passive"))
      (node (ref "U1") (pin "13") (pinfunction "-IN_13") (pintype "input"))
    )
    (net (code "44") (name "Net-(U1D-OUT)") (class "Default")
      (node (ref "R9") (pin "1") (pinfunction "1_1") (pintype "passive"))
      (node (ref "U1") (pin "14") (pinfunction "OUT_14") (pintype "output"))
      (node (ref "U3") (pin "3") (pinfunction "+IN_3") (pintype "input"))
    )
    (net (code "45") (name "Net-(U2A-+IN)") (class "Default")
      (node (ref "R13") (pin "1") (pinfunction "1_1") (pintype "passive"))
      (node (ref "U2") (pin "3") (pinfunction "+IN_3") (pintype "input"))
      (node (ref "U3") (pin "8") (pinfunction "OUT_8") (pintype "output"))
    )
    (net (code "46") (name "Net-(U2B-+IN)") (class "Default")
      (node (ref "R35") (pin "1") (pinfunction "1_1") (pintype "passive"))
      (node (ref "U2") (pin "10") (pinfunction "+IN_10") (pintype "input"))
      (node (ref "U3") (pin "14") (pinfunction "OUT_14") (pintype "output"))
    )
    (net (code "47") (name "Net-(U2C-+IN)") (class "Default")
      (node (ref "R60") (pin "1") (pinfunction "1_1") (pintype "passive"))
      (node (ref "U2") (pin "5") (pinfunction "+IN_5") (pintype "input"))
      (node (ref "U9") (pin "8") (pinfunction "OUT_8") (pintype "output"))
    )
    (net (code "48") (name "Net-(U3A--IN)") (class "Default")
      (node (ref "R12") (pin "2") (pinfunction "2_2") (pintype "passive"))
      (node (ref "R19") (pin "2") (pinfunction "2_2") (pintype "passive"))
      (node (ref "R21") (pin "2") (pinfunction "2_2") (pintype "passive"))
      (node (ref "R3") (pin "2") (pinfunction "2_2") (pintype "passive"))
      (node (ref "T1") (pin "E") (pinfunction "E_E") (pintype "passive"))
      (node (ref "U3") (pin "2") (pinfunction "-IN_2") (pintype "input"))
    )
    (net (code "49") (name "Net-(U3A-OUT)") (class "Default")
      (node (ref "T1") (pin "B") (pinfunction "B_B") (pintype "passive"))
      (node (ref "U3") (pin "1") (pinfunction "OUT_1") (pintype "output"))
    )
    (net (code "50") (name "Net-(U3B-+IN)") (class "Default")
      (node (ref "C2") (pin "1") (pinfunction "1_1") (pintype "passive"))
      (node (ref "R12") (pin "1") (pinfunction "1_1") (pintype "passive"))
      (node (ref "R14") (pin "2") (pinfunction "2_2") (pintype "passive"))
      (node (ref "U3") (pin "10") (pinfunction "+IN_10") (pintype "input"))
    )
    (net (code "51") (name "Net-(U3B--IN)") (class "Default")
      (node (ref "R11") (pin "1") (pinfunction "1_1") (pintype "passive"))
      (node (ref "R13") (pin "2") (pinfunction "2_2") (pintype "passive"))
      (node (ref "U3") (pin "9") (pinfunction "-IN_9") (pintype "input"))
    )
    (net (code "52") (name "Net-(U3C-+IN)") (class "Default")
      (node (ref "R34") (pin "1") (pinfunction "1_1") (pintype "passive"))
      (node (ref "U3") (pin "5") (pinfunction "+IN_5") (pintype "input"))
      (node (ref "U4") (pin "14") (pinfunction "OUT_14") (pintype "output"))
    )
    (net (code "53") (name "Net-(U3C--IN)") (class "Default")
      (node (ref "R26") (pin "2") (pinfunction "2_2") (pintype "passive"))
      (node (ref "R37") (pin "2") (pinfunction "2_2") (pintype "passive"))
      (node (ref "R42") (pin "2") (pinfunction "2_2") (pintype "passive"))
      (node (ref "R44") (pin "2") (pinfunction "2_2") (pintype "passive"))
      (node (ref "T3") (pin "E") (pinfunction "E_E") (pintype "passive"))
      (node (ref "U3") (pin "6") (pinfunction "-IN_6") (pintype "input"))
    )
    (net (code "54") (name "Net-(U3C-OUT)") (class "Default")
      (node (ref "T3") (pin "B") (pinfunction "B_B") (pintype "passive"))
      (node (ref "U3") (pin "7") (pinfunction "OUT_7") (pintype "output"))
    )
    (net (code "55") (name "Net-(U3D-+IN)") (class "Default")
      (node (ref "C4") (pin "1") (pinfunction "1_1") (pintype "passive"))
      (node (ref "R36") (pin "2") (pinfunction "2_2") (pintype "passive"))
      (node (ref "R37") (pin "1") (pinfunction "1_1") (pintype "passive"))
      (node (ref "U3") (pin "12") (pinfunction "+IN_12") (pintype "input"))
    )
    (net (code "56") (name "Net-(U3D--IN)") (class "Default")
      (node (ref "R35") (pin "2") (pinfunction "2_2") (pintype "passive"))
      (node (ref "R50") (pin "1") (pinfunction "1_1") (pintype "passive"))
      (node (ref "U3") (pin "13") (pinfunction "-IN_13") (pintype "input"))
    )
    (net (code "57") (name "Net-(U4A-+IN)") (class "Default")
      (node (ref "R42") (pin "1") (pinfunction "1_1") (pintype "passive"))
      (node (ref "R43") (pin "2") (pinfunction "2_2") (pintype "passive"))
      (node (ref "R44") (pin "1") (pinfunction "1_1") (pintype "passive"))
      (node (ref "U4") (pin "3") (pinfunction "+IN_3") (pintype "input"))
    )
    (net (code "58") (name "Net-(U4B--IN)") (class "Default")
      (node (ref "R46") (pin "2") (pinfunction "2_2") (pintype "passive"))
      (node (ref "U4") (pin "8") (pinfunction "OUT_8") (pintype "output"))
      (node (ref "U4") (pin "9") (pinfunction "-IN_9") (pintype "input"))
    )
    (net (code "59") (name "Net-(U4C-+IN)") (class "Default")
      (node (ref "R46") (pin "1") (pinfunction "1_1") (pintype "passive"))
      (node (ref "R48") (pin "1") (pinfunction "1_1") (pintype "passive"))
      (node (ref "U4") (pin "5") (pinfunction "+IN_5") (pintype "input"))
    )
    (net (code "60") (name "Net-(U4C--IN)") (class "Default")
      (node (ref "R47") (pin "1") (pinfunction "1_1") (pintype "passive"))
      (node (ref "R49") (pin "1") (pinfunction "1_1") (pintype "passive"))
      (node (ref "U4") (pin "6") (pinfunction "-IN_6") (pintype "input"))
    )
    (net (code "61") (name "Net-(U4C-OUT)") (class "Default")
      (node (ref "R28") (pin "2") (pinfunction "2_2") (pintype "passive"))
      (node (ref "R49") (pin "2") (pinfunction "2_2") (pintype "passive"))
      (node (ref "U4") (pin "7") (pinfunction "OUT_7") (pintype "output"))
    )
    (net (code "62") (name "Net-(U4D-+IN)") (class "Default")
      (node (ref "C3") (pin "1") (pinfunction "1_1") (pintype "passive"))
      (node (ref "R28") (pin "1") (pinfunction "1_1") (pintype "passive"))
      (node (ref "R29") (pin "2") (pinfunction "2_2") (pintype "passive"))
      (node (ref "U4") (pin "12") (pinfunction "+IN_12") (pintype "input"))
    )
    (net (code "63") (name "Net-(U4D--IN)") (class "Default")
      (node (ref "R33") (pin "1") (pinfunction "1_1") (pintype "passive"))
      (node (ref "R34") (pin "2") (pinfunction "2_2") (pintype "passive"))
      (node (ref "U4") (pin "13") (pinfunction "-IN_13") (pintype "input"))
    )
    (net (code "64") (name "Net-(U7A-+IN)") (class "Default")
      (node (ref "R67") (pin "1") (pinfunction "1_1") (pintype "passive"))
      (node (ref "R68") (pin "2") (pinfunction "2_2") (pintype "passive"))
      (node (ref "R69") (pin "1") (pinfunction "1_1") (pintype "passive"))
      (node (ref "U7") (pin "3") (pinfunction "+IN_3") (pintype "input"))
    )
    (net (code "65") (name "Net-(U7B--IN)") (class "Default")
      (node (ref "R71") (pin "2") (pinfunction "2_2") (pintype "passive"))
      (node (ref "U7") (pin "8") (pinfunction "OUT_8") (pintype "output"))
      (node (ref "U7") (pin "9") (pinfunction "-IN_9") (pintype "input"))
    )
    (net (code "66") (name "Net-(U7C-+IN)") (class "Default")
      (node (ref "R71") (pin "1") (pinfunction "1_1") (pintype "passive"))
      (node (ref "R73") (pin "1") (pinfunction "1_1") (pintype "passive"))
      (node (ref "U7") (pin "5") (pinfunction "+IN_5") (pintype "input"))
    )
    (net (code "67") (name "Net-(U7C--IN)") (class "Default")
      (node (ref "R72") (pin "1") (pinfunction "1_1") (pintype "passive"))
      (node (ref "R74") (pin "1") (pinfunction "1_1") (pintype "passive"))
      (node (ref "U7") (pin "6") (pinfunction "-IN_6") (pintype "input"))
    )
    (net (code "68") (name "Net-(U7C-OUT)") (class "Default")
      (node (ref "R53") (pin "2") (pinfunction "2_2") (pintype "passive"))
      (node (ref "R74") (pin "2") (pinfunction "2_2") (pintype "passive"))
      (node (ref "U7") (pin "7") (pinfunction "OUT_7") (pintype "output"))
    )
    (net (code "69") (name "Net-(U7D-+IN)") (class "Default")
      (node (ref "C5") (pin "1") (pinfunction "1_1") (pintype "passive"))
      (node (ref "R53") (pin "1") (pinfunction "1_1") (pintype "passive"))
      (node (ref "R54") (pin "2") (pinfunction "2_2") (pintype "passive"))
      (node (ref "U7") (pin "12") (pinfunction "+IN_12") (pintype "input"))
    )
    (net (code "70") (name "Net-(U7D--IN)") (class "Default")
      (node (ref "R58") (pin "1") (pinfunction "1_1") (pintype "passive"))
      (node (ref "R59") (pin "2") (pinfunction "2_2") (pintype "passive"))
      (node (ref "U7") (pin "13") (pinfunction "-IN_13") (pintype "input"))
    )
    (net (code "71") (name "Net-(U7D-OUT)") (class "Default")
      (node (ref "R59") (pin "1") (pinfunction "1_1") (pintype "passive"))
      (node (ref "U7") (pin "14") (pinfunction "OUT_14") (pintype "output"))
      (node (ref "U9") (pin "3") (pinfunction "+IN_3") (pintype "input"))
    )
    (net (code "72") (name "Net-(U9A--IN)") (class "Default")
      (node (ref "R51") (pin "2") (pinfunction "2_2") (pintype "passive"))
      (node (ref "R62") (pin "2") (pinfunction "2_2") (pintype "passive"))
      (node (ref "R67") (pin "2") (pinfunction "2_2") (pintype "passive"))
      (node (ref "R69") (pin "2") (pinfunction "2_2") (pintype "passive"))
      (node (ref "T5") (pin "E") (pinfunction "E_E") (pintype "passive"))
      (node (ref "U9") (pin "2") (pinfunction "-IN_2") (pintype "input"))
    )
    (net (code "73") (name "Net-(U9A-OUT)") (class "Default")
      (node (ref "T5") (pin "B") (pinfunction "B_B") (pintype "passive"))
      (node (ref "U9") (pin "1") (pinfunction "OUT_1") (pintype "output"))
    )
    (net (code "74") (name "Net-(U9B-+IN)") (class "Default")
      (node (ref "C6") (pin "1") (pinfunction "1_1") (pintype "passive"))
      (node (ref "R61") (pin "2") (pinfunction "2_2") (pintype "passive"))
      (node (ref "R62") (pin "1") (pinfunction "1_1") (pintype "passive"))
      (node (ref "U9") (pin "10") (pinfunction "+IN_10") (pintype "input"))
    )
    (net (code "75") (name "Net-(U9B--IN)") (class "Default")
      (node (ref "R60") (pin "2") (pinfunction "2_2") (pintype "passive"))
      (node (ref "R75") (pin "1") (pinfunction "1_1") (pintype "passive"))
      (node (ref "U9") (pin "9") (pinfunction "-IN_9") (pintype "input"))
    )
  )
)
